# optoIsolatorBoard.net
KiCad netlist of a schematic drawn in Altium Designer
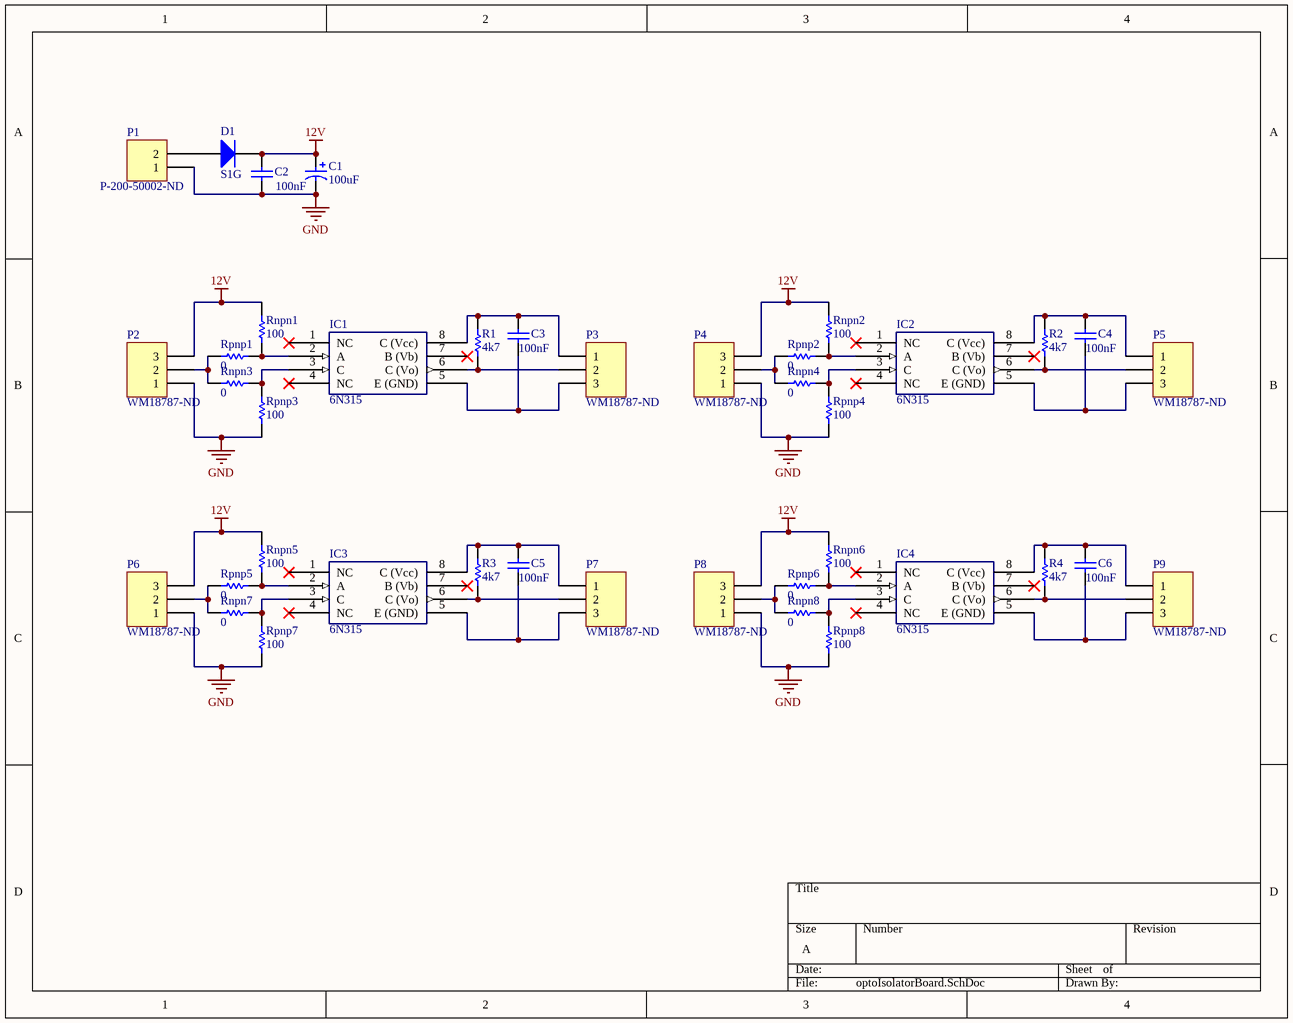
[diagram p0: optoIsolatorBoard.SchDoc]

(export (version "E")
  (design (tool "Eeschema 10.0.6"))
  (components
    (comp (ref "C1")
      (value "100uF")
      (footprint "CAP4-8X10")
      (description "electrolytic capacitor")
      (libsource (lib "hepek_lib") (part "cap5-8x10"))
    )
    (comp (ref "C2")
      (value "100nF")
      (footprint "1206_cap")
      (description "Capacitor")
      (fields (field (name "PUBLISHER") "Altium Limited"))
      (libsource (lib "hepek_lib") (part "cap_1206"))
    )
    (comp (ref "C3")
      (value "100nF")
      (footprint "1206_cap")
      (description "Capacitor")
      (fields (field (name "Comment") "cap_1206") (field (name "PUBLISHER") "Altium Limited"))
      (libsource (lib "hepek_lib") (part "cap_1206"))
    )
    (comp (ref "C4")
      (value "100nF")
      (footprint "1206_cap")
      (description "Capacitor")
      (fields (field (name "Comment") "cap_1206") (field (name "PUBLISHER") "Altium Limited"))
      (libsource (lib "hepek_lib") (part "cap_1206"))
    )
    (comp (ref "C5")
      (value "100nF")
      (footprint "1206_cap")
      (description "Capacitor")
      (fields (field (name "Comment") "cap_1206") (field (name "PUBLISHER") "Altium Limited"))
      (libsource (lib "hepek_lib") (part "cap_1206"))
    )
    (comp (ref "C6")
      (value "100nF")
      (footprint "1206_cap")
      (description "Capacitor")
      (fields (field (name "Comment") "cap_1206") (field (name "PUBLISHER") "Altium Limited"))
      (libsource (lib "hepek_lib") (part "cap_1206"))
    )
    (comp (ref "D1")
      (value "S1G")
      (footprint "DO-214AC(SMA)")
      (description "High Conductance Fast Diode")
      (fields (field (name "PUBLISHER") "Altium Limited"))
      (libsource (lib "hepek_lib") (part "S1G"))
    )
    (comp (ref "IC1")
      (value "6N315")
      (footprint "dip8 smd")
      (description "Single Channel, High Speed  Optocouplers")
      (libsource (lib "hepek_lib") (part "6N315"))
    )
    (comp (ref "IC2")
      (value "6N315")
      (footprint "dip8 smd")
      (description "Single Channel, High Speed  Optocouplers")
      (libsource (lib "hepek_lib") (part "6N315"))
    )
    (comp (ref "IC3")
      (value "6N315")
      (footprint "dip8 smd")
      (description "Single Channel, High Speed  Optocouplers")
      (libsource (lib "hepek_lib") (part "6N315"))
    )
    (comp (ref "IC4")
      (value "6N315")
      (footprint "dip8 smd")
      (description "Single Channel, High Speed  Optocouplers")
      (libsource (lib "hepek_lib") (part "6N315"))
    )
    (comp (ref "P1")
      (value "P-200-50002-ND")
      (footprint "Header2Combination")
      (description "Header, 2-Pin")
      (fields (field (name "PUBLISHER") "Altium Limited"))
      (libsource (lib "hepek_lib") (part "Header2ConPow"))
    )
    (comp (ref "P2")
      (value "WM18787-ND")
      (footprint "molex_conn3")
      (description "Header, 3-Pin")
      (fields (field (name "PUBLISHER") "Altium Limited"))
      (libsource (lib "hepek_lib") (part "Molex conn3"))
    )
    (comp (ref "P3")
      (value "WM18787-ND")
      (footprint "molex_conn3")
      (description "Header, 3-Pin")
      (fields (field (name "PUBLISHER") "Altium Limited"))
      (libsource (lib "") (part "Molex conn3_1"))
    )
    (comp (ref "P4")
      (value "WM18787-ND")
      (footprint "molex_conn3")
      (description "Header, 3-Pin")
      (fields (field (name "PUBLISHER") "Altium Limited"))
      (libsource (lib "hepek_lib") (part "Molex conn3"))
    )
    (comp (ref "P5")
      (value "WM18787-ND")
      (footprint "molex_conn3")
      (description "Header, 3-Pin")
      (fields (field (name "PUBLISHER") "Altium Limited"))
      (libsource (lib "") (part "Molex conn3_1"))
    )
    (comp (ref "P6")
      (value "WM18787-ND")
      (footprint "molex_conn3")
      (description "Header, 3-Pin")
      (fields (field (name "PUBLISHER") "Altium Limited"))
      (libsource (lib "hepek_lib") (part "Molex conn3"))
    )
    (comp (ref "P7")
      (value "WM18787-ND")
      (footprint "molex_conn3")
      (description "Header, 3-Pin")
      (fields (field (name "PUBLISHER") "Altium Limited"))
      (libsource (lib "") (part "Molex conn3_1"))
    )
    (comp (ref "P8")
      (value "WM18787-ND")
      (footprint "molex_conn3")
      (description "Header, 3-Pin")
      (fields (field (name "PUBLISHER") "Altium Limited"))
      (libsource (lib "hepek_lib") (part "Molex conn3"))
    )
    (comp (ref "P9")
      (value "WM18787-ND")
      (footprint "molex_conn3")
      (description "Header, 3-Pin")
      (fields (field (name "PUBLISHER") "Altium Limited"))
      (libsource (lib "") (part "Molex conn3_1"))
    )
    (comp (ref "R1")
      (value "4k7")
      (footprint "1206_res")
      (description "Resistor")
      (fields (field (name "PUBLISHER") "Altium Limited"))
      (libsource (lib "hepek_lib") (part "res"))
    )
    (comp (ref "R2")
      (value "4k7")
      (footprint "1206_res")
      (description "Resistor")
      (fields (field (name "PUBLISHER") "Altium Limited"))
      (libsource (lib "hepek_lib") (part "res"))
    )
    (comp (ref "R3")
      (value "4k7")
      (footprint "1206_res")
      (description "Resistor")
      (fields (field (name "PUBLISHER") "Altium Limited"))
      (libsource (lib "hepek_lib") (part "res"))
    )
    (comp (ref "R4")
      (value "4k7")
      (footprint "1206_res")
      (description "Resistor")
      (fields (field (name "PUBLISHER") "Altium Limited"))
      (libsource (lib "hepek_lib") (part "res"))
    )
    (comp (ref "Rnpn1")
      (value "100")
      (footprint "1206_res")
      (description "Resistor")
      (fields (field (name "PUBLISHER") "Altium Limited"))
      (libsource (lib "hepek_lib") (part "res"))
    )
    (comp (ref "Rnpn2")
      (value "100")
      (footprint "1206_res")
      (description "Resistor")
      (fields (field (name "PUBLISHER") "Altium Limited"))
      (libsource (lib "hepek_lib") (part "res"))
    )
    (comp (ref "Rnpn3")
      (value "0")
      (footprint "1206_res")
      (description "Resistor")
      (fields (field (name "PUBLISHER") "Altium Limited"))
      (libsource (lib "hepek_lib") (part "res"))
    )
    (comp (ref "Rnpn4")
      (value "0")
      (footprint "1206_res")
      (description "Resistor")
      (fields (field (name "PUBLISHER") "Altium Limited"))
      (libsource (lib "hepek_lib") (part "res"))
    )
    (comp (ref "Rnpn5")
      (value "100")
      (footprint "1206_res")
      (description "Resistor")
      (fields (field (name "PUBLISHER") "Altium Limited"))
      (libsource (lib "hepek_lib") (part "res"))
    )
    (comp (ref "Rnpn6")
      (value "100")
      (footprint "1206_res")
      (description "Resistor")
      (fields (field (name "PUBLISHER") "Altium Limited"))
      (libsource (lib "hepek_lib") (part "res"))
    )
    (comp (ref "Rnpn7")
      (value "0")
      (footprint "1206_res")
      (description "Resistor")
      (fields (field (name "PUBLISHER") "Altium Limited"))
      (libsource (lib "hepek_lib") (part "res"))
    )
    (comp (ref "Rnpn8")
      (value "0")
      (footprint "1206_res")
      (description "Resistor")
      (fields (field (name "PUBLISHER") "Altium Limited"))
      (libsource (lib "hepek_lib") (part "res"))
    )
    (comp (ref "Rpnp1")
      (value "0")
      (footprint "1206_res")
      (description "Resistor")
      (fields (field (name "PUBLISHER") "Altium Limited"))
      (libsource (lib "hepek_lib") (part "res"))
    )
    (comp (ref "Rpnp2")
      (value "0")
      (footprint "1206_res")
      (description "Resistor")
      (fields (field (name "PUBLISHER") "Altium Limited"))
      (libsource (lib "hepek_lib") (part "res"))
    )
    (comp (ref "Rpnp3")
      (value "100")
      (footprint "1206_res")
      (description "Resistor")
      (fields (field (name "PUBLISHER") "Altium Limited"))
      (libsource (lib "hepek_lib") (part "res"))
    )
    (comp (ref "Rpnp4")
      (value "100")
      (footprint "1206_res")
      (description "Resistor")
      (fields (field (name "PUBLISHER") "Altium Limited"))
      (libsource (lib "hepek_lib") (part "res"))
    )
    (comp (ref "Rpnp5")
      (value "0")
      (footprint "1206_res")
      (description "Resistor")
      (fields (field (name "PUBLISHER") "Altium Limited"))
      (libsource (lib "hepek_lib") (part "res"))
    )
    (comp (ref "Rpnp6")
      (value "0")
      (footprint "1206_res")
      (description "Resistor")
      (fields (field (name "PUBLISHER") "Altium Limited"))
      (libsource (lib "hepek_lib") (part "res"))
    )
    (comp (ref "Rpnp7")
      (value "100")
      (footprint "1206_res")
      (description "Resistor")
      (fields (field (name "PUBLISHER") "Altium Limited"))
      (libsource (lib "hepek_lib") (part "res"))
    )
    (comp (ref "Rpnp8")
      (value "100")
      (footprint "1206_res")
      (description "Resistor")
      (fields (field (name "PUBLISHER") "Altium Limited"))
      (libsource (lib "hepek_lib") (part "res"))
    )
  )
  (nets
    (net (code "1") (name "12V") (class "Default")
      (node (ref "C1") (pin "1") (pinfunction "1_1") (pintype "passive"))
      (node (ref "C2") (pin "2") (pinfunction "2_2") (pintype "passive"))
      (node (ref "D1") (pin "2") (pinfunction "K_2") (pintype "passive"))
      (node (ref "P2") (pin "3") (pinfunction "3_3") (pintype "passive"))
      (node (ref "P4") (pin "3") (pinfunction "3_3") (pintype "passive"))
      (node (ref "P6") (pin "3") (pinfunction "3_3") (pintype "passive"))
      (node (ref "P8") (pin "3") (pinfunction "3_3") (pintype "passive"))
      (node (ref "Rnpn1") (pin "1") (pinfunction "1_1") (pintype "passive"))
      (node (ref "Rnpn2") (pin "1") (pinfunction "1_1") (pintype "passive"))
      (node (ref "Rnpn5") (pin "1") (pinfunction "1_1") (pintype "passive"))
      (node (ref "Rnpn6") (pin "1") (pinfunction "1_1") (pintype "passive"))
    )
    (net (code "2") (name "GND") (class "Default")
      (node (ref "C1") (pin "2") (pinfunction "2_2") (pintype "passive"))
      (node (ref "C2") (pin "1") (pinfunction "1_1") (pintype "passive"))
      (node (ref "P1") (pin "1") (pinfunction "1_1") (pintype "passive"))
      (node (ref "P2") (pin "1") (pinfunction "1_1") (pintype "passive"))
      (node (ref "P4") (pin "1") (pinfunction "1_1") (pintype "passive"))
      (node (ref "P6") (pin "1") (pinfunction "1_1") (pintype "passive"))
      (node (ref "P8") (pin "1") (pinfunction "1_1") (pintype "passive"))
      (node (ref "Rpnp3") (pin "2") (pinfunction "2_2") (pintype "passive"))
      (node (ref "Rpnp4") (pin "2") (pinfunction "2_2") (pintype "passive"))
      (node (ref "Rpnp7") (pin "2") (pinfunction "2_2") (pintype "passive"))
      (node (ref "Rpnp8") (pin "2") (pinfunction "2_2") (pintype "passive"))
    )
    (net (code "3") (name "Net-(D1-A)") (class "Default")
      (node (ref "D1") (pin "1") (pinfunction "A_1") (pintype "passive"))
      (node (ref "P1") (pin "2") (pinfunction "2_2") (pintype "passive"))
    )
    (net (code "4") (name "Net-(IC1-A)") (class "Default")
      (node (ref "IC1") (pin "2") (pinfunction "A_2") (pintype "input"))
      (node (ref "Rnpn1") (pin "2") (pinfunction "2_2") (pintype "passive"))
      (node (ref "Rpnp1") (pin "1") (pinfunction "1_1") (pintype "passive"))
    )
    (net (code "5") (name "Net-(IC1-C)") (class "Default")
      (node (ref "IC1") (pin "3") (pinfunction "C_3") (pintype "input"))
      (node (ref "Rnpn3") (pin "1") (pinfunction "1_1") (pintype "passive"))
      (node (ref "Rpnp3") (pin "1") (pinfunction "1_1") (pintype "passive"))
    )
    (net (code "6") (name "Net-(IC1-C_(Vcc))") (class "Default")
      (node (ref "C3") (pin "2") (pinfunction "2_2") (pintype "passive"))
      (node (ref "IC1") (pin "8") (pinfunction "C_(Vcc)_8") (pintype "passive"))
      (node (ref "P3") (pin "1") (pinfunction "1_1") (pintype "passive"))
      (node (ref "R1") (pin "2") (pinfunction "2_2") (pintype "passive"))
    )
    (net (code "7") (name "Net-(IC1-C_(Vo))") (class "Default")
      (node (ref "IC1") (pin "6") (pinfunction "C_(Vo)_6") (pintype "output"))
      (node (ref "P3") (pin "2") (pinfunction "2_2") (pintype "passive"))
      (node (ref "R1") (pin "1") (pinfunction "1_1") (pintype "passive"))
    )
    (net (code "8") (name "Net-(IC1-E_(GND))") (class "Default")
      (node (ref "C3") (pin "1") (pinfunction "1_1") (pintype "passive"))
      (node (ref "IC1") (pin "5") (pinfunction "E_(GND)_5") (pintype "passive"))
      (node (ref "P3") (pin "3") (pinfunction "3_3") (pintype "passive"))
    )
    (net (code "9") (name "Net-(IC2-A)") (class "Default")
      (node (ref "IC2") (pin "2") (pinfunction "A_2") (pintype "input"))
      (node (ref "Rnpn2") (pin "2") (pinfunction "2_2") (pintype "passive"))
      (node (ref "Rpnp2") (pin "1") (pinfunction "1_1") (pintype "passive"))
    )
    (net (code "10") (name "Net-(IC2-C)") (class "Default")
      (node (ref "IC2") (pin "3") (pinfunction "C_3") (pintype "input"))
      (node (ref "Rnpn4") (pin "1") (pinfunction "1_1") (pintype "passive"))
      (node (ref "Rpnp4") (pin "1") (pinfunction "1_1") (pintype "passive"))
    )
    (net (code "11") (name "Net-(IC2-C_(Vcc))") (class "Default")
      (node (ref "C4") (pin "2") (pinfunction "2_2") (pintype "passive"))
      (node (ref "IC2") (pin "8") (pinfunction "C_(Vcc)_8") (pintype "passive"))
      (node (ref "P5") (pin "1") (pinfunction "1_1") (pintype "passive"))
      (node (ref "R2") (pin "2") (pinfunction "2_2") (pintype "passive"))
    )
    (net (code "12") (name "Net-(IC2-C_(Vo))") (class "Default")
      (node (ref "IC2") (pin "6") (pinfunction "C_(Vo)_6") (pintype "output"))
      (node (ref "P5") (pin "2") (pinfunction "2_2") (pintype "passive"))
      (node (ref "R2") (pin "1") (pinfunction "1_1") (pintype "passive"))
    )
    (net (code "13") (name "Net-(IC2-E_(GND))") (class "Default")
      (node (ref "C4") (pin "1") (pinfunction "1_1") (pintype "passive"))
      (node (ref "IC2") (pin "5") (pinfunction "E_(GND)_5") (pintype "passive"))
      (node (ref "P5") (pin "3") (pinfunction "3_3") (pintype "passive"))
    )
    (net (code "14") (name "Net-(IC3-A)") (class "Default")
      (node (ref "IC3") (pin "2") (pinfunction "A_2") (pintype "input"))
      (node (ref "Rnpn5") (pin "2") (pinfunction "2_2") (pintype "passive"))
      (node (ref "Rpnp5") (pin "1") (pinfunction "1_1") (pintype "passive"))
    )
    (net (code "15") (name "Net-(IC3-C)") (class "Default")
      (node (ref "IC3") (pin "3") (pinfunction "C_3") (pintype "input"))
      (node (ref "Rnpn7") (pin "1") (pinfunction "1_1") (pintype "passive"))
      (node (ref "Rpnp7") (pin "1") (pinfunction "1_1") (pintype "passive"))
    )
    (net (code "16") (name "Net-(IC3-C_(Vcc))") (class "Default")
      (node (ref "C5") (pin "2") (pinfunction "2_2") (pintype "passive"))
      (node (ref "IC3") (pin "8") (pinfunction "C_(Vcc)_8") (pintype "passive"))
      (node (ref "P7") (pin "1") (pinfunction "1_1") (pintype "passive"))
      (node (ref "R3") (pin "2") (pinfunction "2_2") (pintype "passive"))
    )
    (net (code "17") (name "Net-(IC3-C_(Vo))") (class "Default")
      (node (ref "IC3") (pin "6") (pinfunction "C_(Vo)_6") (pintype "output"))
      (node (ref "P7") (pin "2") (pinfunction "2_2") (pintype "passive"))
      (node (ref "R3") (pin "1") (pinfunction "1_1") (pintype "passive"))
    )
    (net (code "18") (name "Net-(IC3-E_(GND))") (class "Default")
      (node (ref "C5") (pin "1") (pinfunction "1_1") (pintype "passive"))
      (node (ref "IC3") (pin "5") (pinfunction "E_(GND)_5") (pintype "passive"))
      (node (ref "P7") (pin "3") (pinfunction "3_3") (pintype "passive"))
    )
    (net (code "19") (name "Net-(IC4-A)") (class "Default")
      (node (ref "IC4") (pin "2") (pinfunction "A_2") (pintype "input"))
      (node (ref "Rnpn6") (pin "2") (pinfunction "2_2") (pintype "passive"))
      (node (ref "Rpnp6") (pin "1") (pinfunction "1_1") (pintype "passive"))
    )
    (net (code "20") (name "Net-(IC4-C)") (class "Default")
      (node (ref "IC4") (pin "3") (pinfunction "C_3") (pintype "input"))
      (node (ref "Rnpn8") (pin "1") (pinfunction "1_1") (pintype "passive"))
      (node (ref "Rpnp8") (pin "1") (pinfunction "1_1") (pintype "passive"))
    )
    (net (code "21") (name "Net-(IC4-C_(Vcc))") (class "Default")
      (node (ref "C6") (pin "2") (pinfunction "2_2") (pintype "passive"))
      (node (ref "IC4") (pin "8") (pinfunction "C_(Vcc)_8") (pintype "passive"))
      (node (ref "P9") (pin "1") (pinfunction "1_1") (pintype "passive"))
      (node (ref "R4") (pin "2") (pinfunction "2_2") (pintype "passive"))
    )
    (net (code "22") (name "Net-(IC4-C_(Vo))") (class "Default")
      (node (ref "IC4") (pin "6") (pinfunction "C_(Vo)_6") (pintype "output"))
      (node (ref "P9") (pin "2") (pinfunction "2_2") (pintype "passive"))
      (node (ref "R4") (pin "1") (pinfunction "1_1") (pintype "passive"))
    )
    (net (code "23") (name "Net-(IC4-E_(GND))") (class "Default")
      (node (ref "C6") (pin "1") (pinfunction "1_1") (pintype "passive"))
      (node (ref "IC4") (pin "5") (pinfunction "E_(GND)_5") (pintype "passive"))
      (node (ref "P9") (pin "3") (pinfunction "3_3") (pintype "passive"))
    )
    (net (code "24") (name "Net-(P2-Pad2)") (class "Default")
      (node (ref "P2") (pin "2") (pinfunction "2_2") (pintype "passive"))
      (node (ref "Rnpn3") (pin "2") (pinfunction "2_2") (pintype "passive"))
      (node (ref "Rpnp1") (pin "2") (pinfunction "2_2") (pintype "passive"))
    )
    (net (code "25") (name "Net-(P4-Pad2)") (class "Default")
      (node (ref "P4") (pin "2") (pinfunction "2_2") (pintype "passive"))
      (node (ref "Rnpn4") (pin "2") (pinfunction "2_2") (pintype "passive"))
      (node (ref "Rpnp2") (pin "2") (pinfunction "2_2") (pintype "passive"))
    )
    (net (code "26") (name "Net-(P6-Pad2)") (class "Default")
      (node (ref "P6") (pin "2") (pinfunction "2_2") (pintype "passive"))
      (node (ref "Rnpn7") (pin "2") (pinfunction "2_2") (pintype "passive"))
      (node (ref "Rpnp5") (pin "2") (pinfunction "2_2") (pintype "passive"))
    )
    (net (code "27") (name "Net-(P8-Pad2)") (class "Default")
      (node (ref "P8") (pin "2") (pinfunction "2_2") (pintype "passive"))
      (node (ref "Rnpn8") (pin "2") (pinfunction "2_2") (pintype "passive"))
      (node (ref "Rpnp6") (pin "2") (pinfunction "2_2") (pintype "passive"))
    )
    (net (code "28") (name "unconnected-(IC1-B_(Vb)-Pad7)") (class "Default")
      (node (ref "IC1") (pin "7") (pinfunction "B_(Vb)_7") (pintype "passive+no_connect"))
    )
    (net (code "29") (name "unconnected-(IC1-NC-Pad1)") (class "Default")
      (node (ref "IC1") (pin "1") (pinfunction "NC_1") (pintype "tri_state+no_connect"))
    )
    (net (code "30") (name "unconnected-(IC1-NC-Pad4)") (class "Default")
      (node (ref "IC1") (pin "4") (pinfunction "NC_4") (pintype "tri_state+no_connect"))
    )
    (net (code "31") (name "unconnected-(IC2-B_(Vb)-Pad7)") (class "Default")
      (node (ref "IC2") (pin "7") (pinfunction "B_(Vb)_7") (pintype "passive+no_connect"))
    )
    (net (code "32") (name "unconnected-(IC2-NC-Pad1)") (class "Default")
      (node (ref "IC2") (pin "1") (pinfunction "NC_1") (pintype "tri_state+no_connect"))
    )
    (net (code "33") (name "unconnected-(IC2-NC-Pad4)") (class "Default")
      (node (ref "IC2") (pin "4") (pinfunction "NC_4") (pintype "tri_state+no_connect"))
    )
    (net (code "34") (name "unconnected-(IC3-B_(Vb)-Pad7)") (class "Default")
      (node (ref "IC3") (pin "7") (pinfunction "B_(Vb)_7") (pintype "passive+no_connect"))
    )
    (net (code "35") (name "unconnected-(IC3-NC-Pad1)") (class "Default")
      (node (ref "IC3") (pin "1") (pinfunction "NC_1") (pintype "tri_state+no_connect"))
    )
    (net (code "36") (name "unconnected-(IC3-NC-Pad4)") (class "Default")
      (node (ref "IC3") (pin "4") (pinfunction "NC_4") (pintype "tri_state+no_connect"))
    )
    (net (code "37") (name "unconnected-(IC4-B_(Vb)-Pad7)") (class "Default")
      (node (ref "IC4") (pin "7") (pinfunction "B_(Vb)_7") (pintype "passive+no_connect"))
    )
    (net (code "38") (name "unconnected-(IC4-NC-Pad1)") (class "Default")
      (node (ref "IC4") (pin "1") (pinfunction "NC_1") (pintype "tri_state+no_connect"))
    )
    (net (code "39") (name "unconnected-(IC4-NC-Pad4)") (class "Default")
      (node (ref "IC4") (pin "4") (pinfunction "NC_4") (pintype "tri_state+no_connect"))
    )
  )
)
